# WIFI.net
KiCad netlist of a schematic drawn in Altium Designer
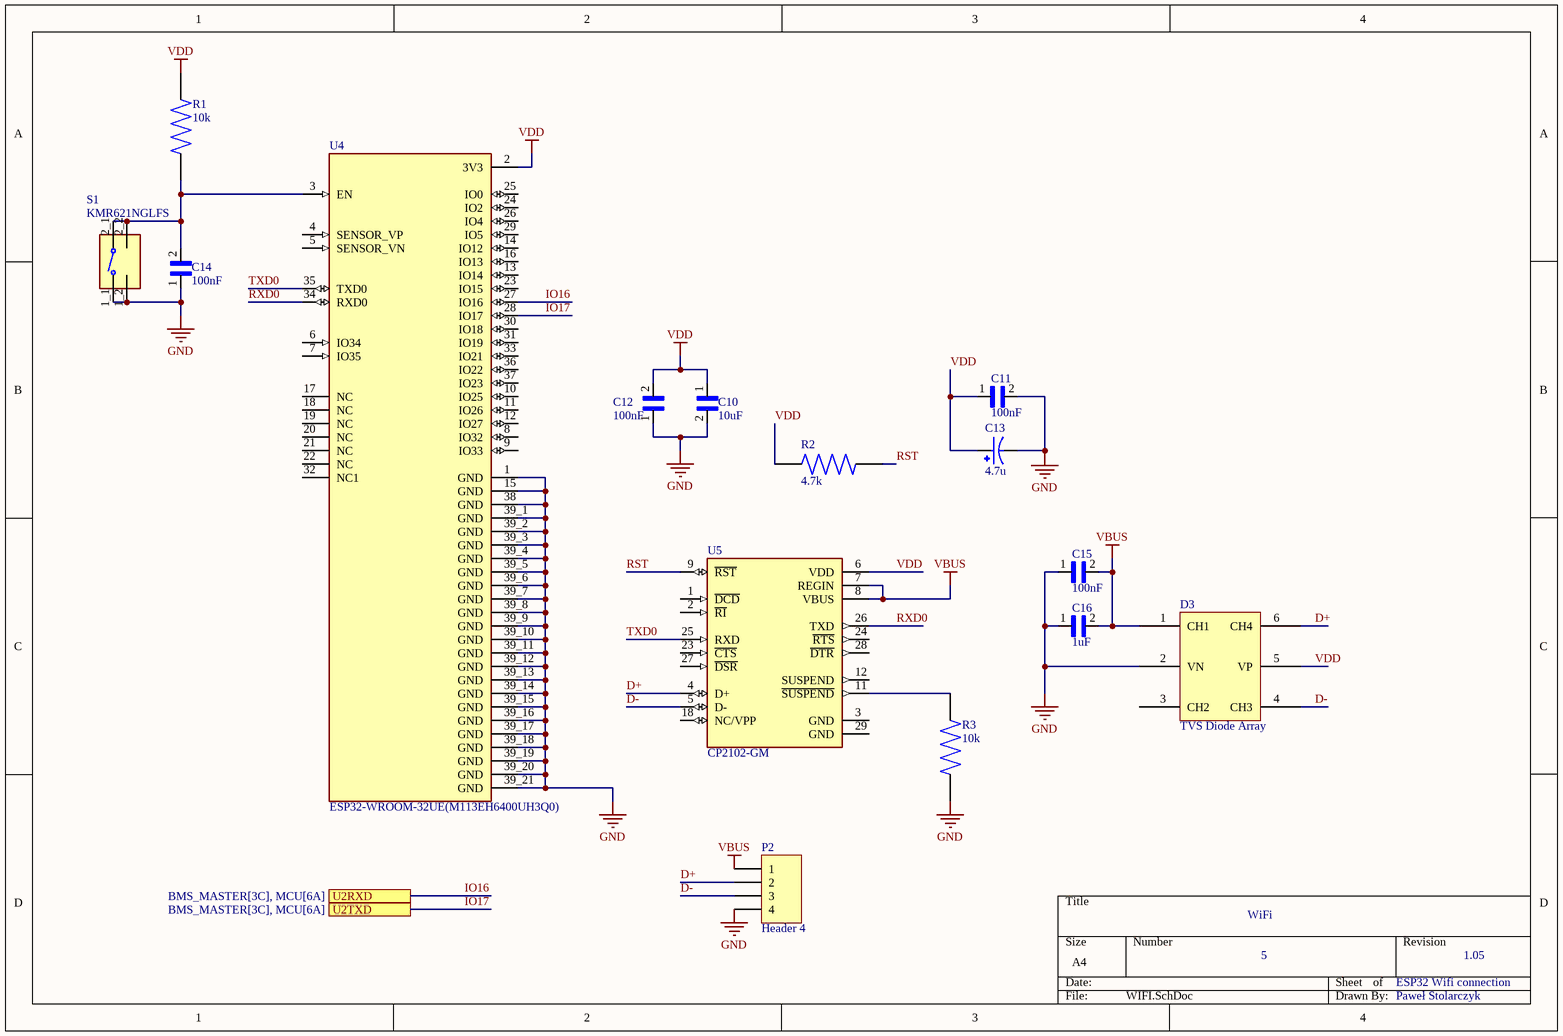
[diagram p0: WIFI.SchDoc]

(export (version "E")
  (design (tool "Eeschema 10.0.6"))
  (components
    (comp (ref "C10")
      (value "10uF")
      (footprint "CAPC1608X90N")
      (description "0.1ÂµF Â±5% 16V Ceramic Capacitor X7R 0603 (1608 Metric)")
      (fields (field (name "MP") "C0603C104J4RAC") (field (name "MF") "KEMET"))
      (libsource (lib "") (part "C0603C104J4RAC_2"))
    )
    (comp (ref "C11")
      (value "100nF")
      (footprint "CAPC1608X90N")
      (description "0.1ÂµF Â±5% 16V Ceramic Capacitor X7R 0603 (1608 Metric)")
      (fields (field (name "MP") "C0603C104J4RAC") (field (name "MF") "KEMET"))
      (libsource (lib "") (part "C0603C104J4RAC_1"))
    )
    (comp (ref "C12")
      (value "100nF")
      (footprint "CAPC1608X90N")
      (description "0.1ÂµF Â±5% 16V Ceramic Capacitor X7R 0603 (1608 Metric)")
      (fields (field (name "MP") "C0603C104J4RAC") (field (name "MF") "KEMET"))
      (libsource (lib "C0603C104J4RAC") (part "C0603C104J4RAC"))
    )
    (comp (ref "C13")
      (value "4.7u")
      (footprint "CAP_EEE1CA100SR")
      (description "10ÂµF 16V Aluminum Electrolytic Capacitors Radial, Can - SMD 2000 Hrs @ 85Â°C")
      (fields (field (name "MF") "Panasonic") (field (name "DIGI-KEY_PART_NUMBER") "PCE3878CT-ND"))
      (libsource (lib "EEE1CA100SR") (part "EEE1CA100SR"))
    )
    (comp (ref "C14")
      (value "100nF")
      (footprint "CAPC1608X90N")
      (description "0.1ÂµF Â±5% 16V Ceramic Capacitor X7R 0603 (1608 Metric)")
      (fields (field (name "MP") "C0603C104J4RAC") (field (name "MF") "KEMET"))
      (libsource (lib "C0603C104J4RAC") (part "C0603C104J4RAC"))
    )
    (comp (ref "C15")
      (value "100nF")
      (footprint "CAPC1608X90N")
      (description "0.1ÂµF Â±5% 16V Ceramic Capacitor X7R 0603 (1608 Metric)")
      (fields (field (name "MP") "C0603C104J4RAC") (field (name "MF") "KEMET"))
      (libsource (lib "") (part "C0603C104J4RAC_1"))
    )
    (comp (ref "C16")
      (value "1uF")
      (footprint "CAPC1608X90N")
      (description "0.1ÂµF Â±5% 16V Ceramic Capacitor X7R 0603 (1608 Metric)")
      (fields (field (name "MP") "C0603C104J4RAC") (field (name "MF") "KEMET"))
      (libsource (lib "") (part "C0603C104J4RAC_1"))
    )
    (comp (ref "D3")
      (value "TVS Diode Array")
      (footprint "SOT23-6-V2")
      (description "Ultra-Low Capacitance TVS Diode Array")
      (libsource (lib "AOZ8105") (part "AOZ8105"))
    )
    (comp (ref "P2")
      (value "Header 4")
      (footprint "HDR1X4")
      (description "Header, 4-Pin")
      (fields (field (name "PUBLISHER") "Altium Limited"))
      (libsource (lib "Miscellaneous Connectors") (part "Header 4"))
    )
    (comp (ref "R1")
      (value "10k")
      (footprint "0402")
      (fields (field (name "MP") "RK73H1JTTD1102F"))
      (libsource (lib "RK73H1JTTD1102F") (part "RK73H1JTTD1102F"))
    )
    (comp (ref "R2")
      (value "4.7k")
      (footprint "0402")
      (fields (field (name "MP") "RK73H1JTTD1102F"))
      (libsource (lib "RK73H1JTTD1102F") (part "RK73H1JTTD1102F"))
    )
    (comp (ref "R3")
      (value "10k")
      (footprint "0402")
      (fields (field (name "MP") "RK73H1JTTD1102F"))
      (libsource (lib "RK73H1JTTD1102F") (part "RK73H1JTTD1102F"))
    )
    (comp (ref "S1")
      (value "KMR621NGLFS")
      (footprint "SW_KMR621NGLFS")
      (description "Tactile Switch SPST-NO Top Actuated Surface Mount")
      (fields (field (name "MF") "C&K") (field (name "MP") "KMR621NG LFS"))
      (libsource (lib "KMR621NGLFS") (part "KMR621NGLFS"))
    )
    (comp (ref "U4")
      (value "ESP32-WROOM-32UE(M113EH6400UH3Q0)")
      (footprint "MODULE_ESP32-WROOM-32UE(M113EH6400UH3Q0)")
      (fields (field (name "MF") "Espressif Systems"))
      (libsource (lib "ESP32-WROOM-32UE_M113EH6400UH3Q0_") (part "ESP32-WROOM-32UE(M113EH6400UH3Q0)"))
    )
    (comp (ref "U5")
      (value "CP2102-GM")
      (footprint "QFN50P500X500X100-29N")
      (description "USB Bridge, USB to UART USB 2.0 UART Interface 28-QFN (5x5)")
      (fields (field (name "MF") "Silicon Labs"))
      (libsource (lib "CP2102-GM") (part "CP2102-GM"))
    )
  )
  (nets
    (net (code "1") (name "/D+") (class "Default")
      (node (ref "D3") (pin "6") (pinfunction "CH4_6") (pintype "passive"))
      (node (ref "P2") (pin "2") (pinfunction "2_2") (pintype "passive"))
      (node (ref "U5") (pin "4") (pinfunction "D+_4") (pintype "bidirectional"))
    )
    (net (code "2") (name "/D-") (class "Default")
      (node (ref "D3") (pin "4") (pinfunction "CH3_4") (pintype "passive"))
      (node (ref "P2") (pin "3") (pinfunction "3_3") (pintype "passive"))
      (node (ref "U5") (pin "5") (pinfunction "D-_5") (pintype "bidirectional"))
    )
    (net (code "3") (name "/IO16") (class "Default")
      (node (ref "U4") (pin "27") (pinfunction "IO16_27") (pintype "bidirectional"))
    )
    (net (code "4") (name "/IO17") (class "Default")
      (node (ref "U4") (pin "28") (pinfunction "IO17_28") (pintype "bidirectional"))
    )
    (net (code "5") (name "/RST") (class "Default")
      (node (ref "R2") (pin "1") (pinfunction "1_1") (pintype "passive"))
      (node (ref "U5") (pin "9") (pinfunction "~{RST}_9") (pintype "bidirectional"))
    )
    (net (code "6") (name "/RXD0") (class "Default")
      (node (ref "U4") (pin "34") (pinfunction "RXD0_34") (pintype "bidirectional"))
      (node (ref "U5") (pin "26") (pinfunction "TXD_26") (pintype "output"))
    )
    (net (code "7") (name "/TXD0") (class "Default")
      (node (ref "U4") (pin "35") (pinfunction "TXD0_35") (pintype "bidirectional"))
      (node (ref "U5") (pin "25") (pinfunction "RXD_25") (pintype "input"))
    )
    (net (code "8") (name "GND") (class "Default")
      (node (ref "C10") (pin "2") (pinfunction "2_2") (pintype "passive"))
      (node (ref "C11") (pin "2") (pinfunction "2_2") (pintype "passive"))
      (node (ref "C12") (pin "1") (pinfunction "1_1") (pintype "passive"))
      (node (ref "C13") (pin "2") (pinfunction "2_2") (pintype "passive"))
      (node (ref "C14") (pin "1") (pinfunction "1_1") (pintype "passive"))
      (node (ref "C15") (pin "1") (pinfunction "1_1") (pintype "passive"))
      (node (ref "C16") (pin "1") (pinfunction "1_1") (pintype "passive"))
      (node (ref "D3") (pin "2") (pinfunction "VN_2") (pintype "passive"))
      (node (ref "P2") (pin "4") (pinfunction "4_4") (pintype "passive"))
      (node (ref "R3") (pin "2") (pinfunction "2_2") (pintype "passive"))
      (node (ref "S1") (pin "1_1") (pinfunction "1_1_1") (pintype "passive"))
      (node (ref "S1") (pin "1_2") (pinfunction "1_1_2") (pintype "passive"))
      (node (ref "U4") (pin "1") (pinfunction "GND_1") (pintype "power_in"))
      (node (ref "U4") (pin "15") (pinfunction "GND_15") (pintype "power_in"))
      (node (ref "U4") (pin "38") (pinfunction "GND_38") (pintype "power_in"))
      (node (ref "U4") (pin "39_1") (pinfunction "GND_39_1") (pintype "power_in"))
      (node (ref "U4") (pin "39_10") (pinfunction "GND_39_10") (pintype "power_in"))
      (node (ref "U4") (pin "39_11") (pinfunction "GND_39_11") (pintype "power_in"))
      (node (ref "U4") (pin "39_12") (pinfunction "GND_39_12") (pintype "power_in"))
      (node (ref "U4") (pin "39_13") (pinfunction "GND_39_13") (pintype "power_in"))
      (node (ref "U4") (pin "39_14") (pinfunction "GND_39_14") (pintype "power_in"))
      (node (ref "U4") (pin "39_15") (pinfunction "GND_39_15") (pintype "power_in"))
      (node (ref "U4") (pin "39_16") (pinfunction "GND_39_16") (pintype "power_in"))
      (node (ref "U4") (pin "39_17") (pinfunction "GND_39_17") (pintype "power_in"))
      (node (ref "U4") (pin "39_18") (pinfunction "GND_39_18") (pintype "power_in"))
      (node (ref "U4") (pin "39_19") (pinfunction "GND_39_19") (pintype "power_in"))
      (node (ref "U4") (pin "39_2") (pinfunction "GND_39_2") (pintype "power_in"))
      (node (ref "U4") (pin "39_20") (pinfunction "GND_39_20") (pintype "power_in"))
      (node (ref "U4") (pin "39_21") (pinfunction "GND_39_21") (pintype "power_in"))
      (node (ref "U4") (pin "39_3") (pinfunction "GND_39_3") (pintype "power_in"))
      (node (ref "U4") (pin "39_4") (pinfunction "GND_39_4") (pintype "power_in"))
      (node (ref "U4") (pin "39_5") (pinfunction "GND_39_5") (pintype "power_in"))
      (node (ref "U4") (pin "39_6") (pinfunction "GND_39_6") (pintype "power_in"))
      (node (ref "U4") (pin "39_7") (pinfunction "GND_39_7") (pintype "power_in"))
      (node (ref "U4") (pin "39_8") (pinfunction "GND_39_8") (pintype "power_in"))
      (node (ref "U4") (pin "39_9") (pinfunction "GND_39_9") (pintype "power_in"))
    )
    (net (code "9") (name "Net-(U4-EN)") (class "Default")
      (node (ref "C14") (pin "2") (pinfunction "2_2") (pintype "passive"))
      (node (ref "R1") (pin "2") (pinfunction "2_2") (pintype "passive"))
      (node (ref "S1") (pin "2_1") (pinfunction "2_2_1") (pintype "passive"))
      (node (ref "S1") (pin "2_2") (pinfunction "2_2_2") (pintype "passive"))
      (node (ref "U4") (pin "3") (pinfunction "EN_3") (pintype "input"))
    )
    (net (code "10") (name "Net-(U5-~{SUSPEND})") (class "Default")
      (node (ref "R3") (pin "1") (pinfunction "1_1") (pintype "passive"))
      (node (ref "U5") (pin "11") (pinfunction "~{SUSPEND}_11") (pintype "output"))
    )
    (net (code "11") (name "VBUS") (class "Default")
      (node (ref "C15") (pin "2") (pinfunction "2_2") (pintype "passive"))
      (node (ref "C16") (pin "2") (pinfunction "2_2") (pintype "passive"))
      (node (ref "D3") (pin "1") (pinfunction "CH1_1") (pintype "passive"))
      (node (ref "P2") (pin "1") (pinfunction "1_1") (pintype "passive"))
      (node (ref "U5") (pin "7") (pinfunction "REGIN_7") (pintype "power_in"))
      (node (ref "U5") (pin "8") (pinfunction "VBUS_8") (pintype "power_in"))
    )
    (net (code "12") (name "VDD") (class "Default")
      (node (ref "C10") (pin "1") (pinfunction "1_1") (pintype "passive"))
      (node (ref "C11") (pin "1") (pinfunction "1_1") (pintype "passive"))
      (node (ref "C12") (pin "2") (pinfunction "2_2") (pintype "passive"))
      (node (ref "C13") (pin "1") (pinfunction "1_1") (pintype "passive"))
      (node (ref "D3") (pin "5") (pinfunction "VP_5") (pintype "passive"))
      (node (ref "R1") (pin "1") (pinfunction "1_1") (pintype "passive"))
      (node (ref "R2") (pin "2") (pinfunction "2_2") (pintype "passive"))
      (node (ref "U4") (pin "2") (pinfunction "3V3_2") (pintype "power_in"))
      (node (ref "U5") (pin "6") (pinfunction "VDD_6") (pintype "power_in"))
    )
    (net (code "13") (name "unconnected-(D3-CH2-Pad3)") (class "Default")
      (node (ref "D3") (pin "3") (pinfunction "CH2_3") (pintype "passive"))
    )
    (net (code "14") (name "unconnected-(U4-IO0-Pad25)") (class "Default")
      (node (ref "U4") (pin "25") (pinfunction "IO0_25") (pintype "bidirectional"))
    )
    (net (code "15") (name "unconnected-(U4-IO2-Pad24)") (class "Default")
      (node (ref "U4") (pin "24") (pinfunction "IO2_24") (pintype "bidirectional"))
    )
    (net (code "16") (name "unconnected-(U4-IO4-Pad26)") (class "Default")
      (node (ref "U4") (pin "26") (pinfunction "IO4_26") (pintype "bidirectional"))
    )
    (net (code "17") (name "unconnected-(U4-IO5-Pad29)") (class "Default")
      (node (ref "U4") (pin "29") (pinfunction "IO5_29") (pintype "bidirectional"))
    )
    (net (code "18") (name "unconnected-(U4-IO12-Pad14)") (class "Default")
      (node (ref "U4") (pin "14") (pinfunction "IO12_14") (pintype "bidirectional"))
    )
    (net (code "19") (name "unconnected-(U4-IO13-Pad16)") (class "Default")
      (node (ref "U4") (pin "16") (pinfunction "IO13_16") (pintype "bidirectional"))
    )
    (net (code "20") (name "unconnected-(U4-IO14-Pad13)") (class "Default")
      (node (ref "U4") (pin "13") (pinfunction "IO14_13") (pintype "bidirectional"))
    )
    (net (code "21") (name "unconnected-(U4-IO15-Pad23)") (class "Default")
      (node (ref "U4") (pin "23") (pinfunction "IO15_23") (pintype "bidirectional"))
    )
    (net (code "22") (name "unconnected-(U4-IO18-Pad30)") (class "Default")
      (node (ref "U4") (pin "30") (pinfunction "IO18_30") (pintype "bidirectional"))
    )
    (net (code "23") (name "unconnected-(U4-IO19-Pad31)") (class "Default")
      (node (ref "U4") (pin "31") (pinfunction "IO19_31") (pintype "bidirectional"))
    )
    (net (code "24") (name "unconnected-(U4-IO21-Pad33)") (class "Default")
      (node (ref "U4") (pin "33") (pinfunction "IO21_33") (pintype "bidirectional"))
    )
    (net (code "25") (name "unconnected-(U4-IO22-Pad36)") (class "Default")
      (node (ref "U4") (pin "36") (pinfunction "IO22_36") (pintype "bidirectional"))
    )
    (net (code "26") (name "unconnected-(U4-IO23-Pad37)") (class "Default")
      (node (ref "U4") (pin "37") (pinfunction "IO23_37") (pintype "bidirectional"))
    )
    (net (code "27") (name "unconnected-(U4-IO25-Pad10)") (class "Default")
      (node (ref "U4") (pin "10") (pinfunction "IO25_10") (pintype "bidirectional"))
    )
    (net (code "28") (name "unconnected-(U4-IO26-Pad11)") (class "Default")
      (node (ref "U4") (pin "11") (pinfunction "IO26_11") (pintype "bidirectional"))
    )
    (net (code "29") (name "unconnected-(U4-IO27-Pad12)") (class "Default")
      (node (ref "U4") (pin "12") (pinfunction "IO27_12") (pintype "bidirectional"))
    )
    (net (code "30") (name "unconnected-(U4-IO32-Pad8)") (class "Default")
      (node (ref "U4") (pin "8") (pinfunction "IO32_8") (pintype "bidirectional"))
    )
    (net (code "31") (name "unconnected-(U4-IO33-Pad9)") (class "Default")
      (node (ref "U4") (pin "9") (pinfunction "IO33_9") (pintype "bidirectional"))
    )
    (net (code "32") (name "unconnected-(U4-IO34-Pad6)") (class "Default")
      (node (ref "U4") (pin "6") (pinfunction "IO34_6") (pintype "input"))
    )
    (net (code "33") (name "unconnected-(U4-IO35-Pad7)") (class "Default")
      (node (ref "U4") (pin "7") (pinfunction "IO35_7") (pintype "input"))
    )
    (net (code "34") (name "unconnected-(U4-NC-Pad17)") (class "Default")
      (node (ref "U4") (pin "17") (pinfunction "NC_17") (pintype "passive"))
    )
    (net (code "35") (name "unconnected-(U4-NC-Pad18)") (class "Default")
      (node (ref "U4") (pin "18") (pinfunction "NC_18") (pintype "passive"))
    )
    (net (code "36") (name "unconnected-(U4-NC-Pad19)") (class "Default")
      (node (ref "U4") (pin "19") (pinfunction "NC_19") (pintype "passive"))
    )
    (net (code "37") (name "unconnected-(U4-NC-Pad20)") (class "Default")
      (node (ref "U4") (pin "20") (pinfunction "NC_20") (pintype "passive"))
    )
    (net (code "38") (name "unconnected-(U4-NC-Pad21)") (class "Default")
      (node (ref "U4") (pin "21") (pinfunction "NC_21") (pintype "passive"))
    )
    (net (code "39") (name "unconnected-(U4-NC-Pad22)") (class "Default")
      (node (ref "U4") (pin "22") (pinfunction "NC_22") (pintype "passive"))
    )
    (net (code "40") (name "unconnected-(U4-NC1-Pad32)") (class "Default")
      (node (ref "U4") (pin "32") (pinfunction "NC1_32") (pintype "passive"))
    )
    (net (code "41") (name "unconnected-(U4-SENSOR_VN-Pad5)") (class "Default")
      (node (ref "U4") (pin "5") (pinfunction "SENSOR_VN_5") (pintype "input"))
    )
    (net (code "42") (name "unconnected-(U4-SENSOR_VP-Pad4)") (class "Default")
      (node (ref "U4") (pin "4") (pinfunction "SENSOR_VP_4") (pintype "input"))
    )
    (net (code "43") (name "unconnected-(U5-GND-Pad3)") (class "Default")
      (node (ref "U5") (pin "3") (pinfunction "GND_3") (pintype "power_in"))
    )
    (net (code "44") (name "unconnected-(U5-GND-Pad29)") (class "Default")
      (node (ref "U5") (pin "29") (pinfunction "GND_29") (pintype "power_in"))
    )
    (net (code "45") (name "unconnected-(U5-NC{slash}VPP-Pad18)") (class "Default")
      (node (ref "U5") (pin "18") (pinfunction "NC/VPP_18") (pintype "bidirectional"))
    )
    (net (code "46") (name "unconnected-(U5-SUSPEND-Pad12)") (class "Default")
      (node (ref "U5") (pin "12") (pinfunction "SUSPEND_12") (pintype "output"))
    )
    (net (code "47") (name "unconnected-(U5-~{CTS}-Pad23)") (class "Default")
      (node (ref "U5") (pin "23") (pinfunction "~{CTS}_23") (pintype "input"))
    )
    (net (code "48") (name "unconnected-(U5-~{DCD}-Pad1)") (class "Default")
      (node (ref "U5") (pin "1") (pinfunction "~{DCD}_1") (pintype "input"))
    )
    (net (code "49") (name "unconnected-(U5-~{DSR}-Pad27)") (class "Default")
      (node (ref "U5") (pin "27") (pinfunction "~{DSR}_27") (pintype "input"))
    )
    (net (code "50") (name "unconnected-(U5-~{DTR}-Pad28)") (class "Default")
      (node (ref "U5") (pin "28") (pinfunction "~{DTR}_28") (pintype "output"))
    )
    (net (code "51") (name "unconnected-(U5-~{RI}-Pad2)") (class "Default")
      (node (ref "U5") (pin "2") (pinfunction "~{RI}_2") (pintype "input"))
    )
    (net (code "52") (name "unconnected-(U5-~{RTS}-Pad24)") (class "Default")
      (node (ref "U5") (pin "24") (pinfunction "~{RTS}_24") (pintype "output"))
    )
  )
)
